# Schaltzeichen.net
KiCad netlist of a schematic drawn in EAGLE
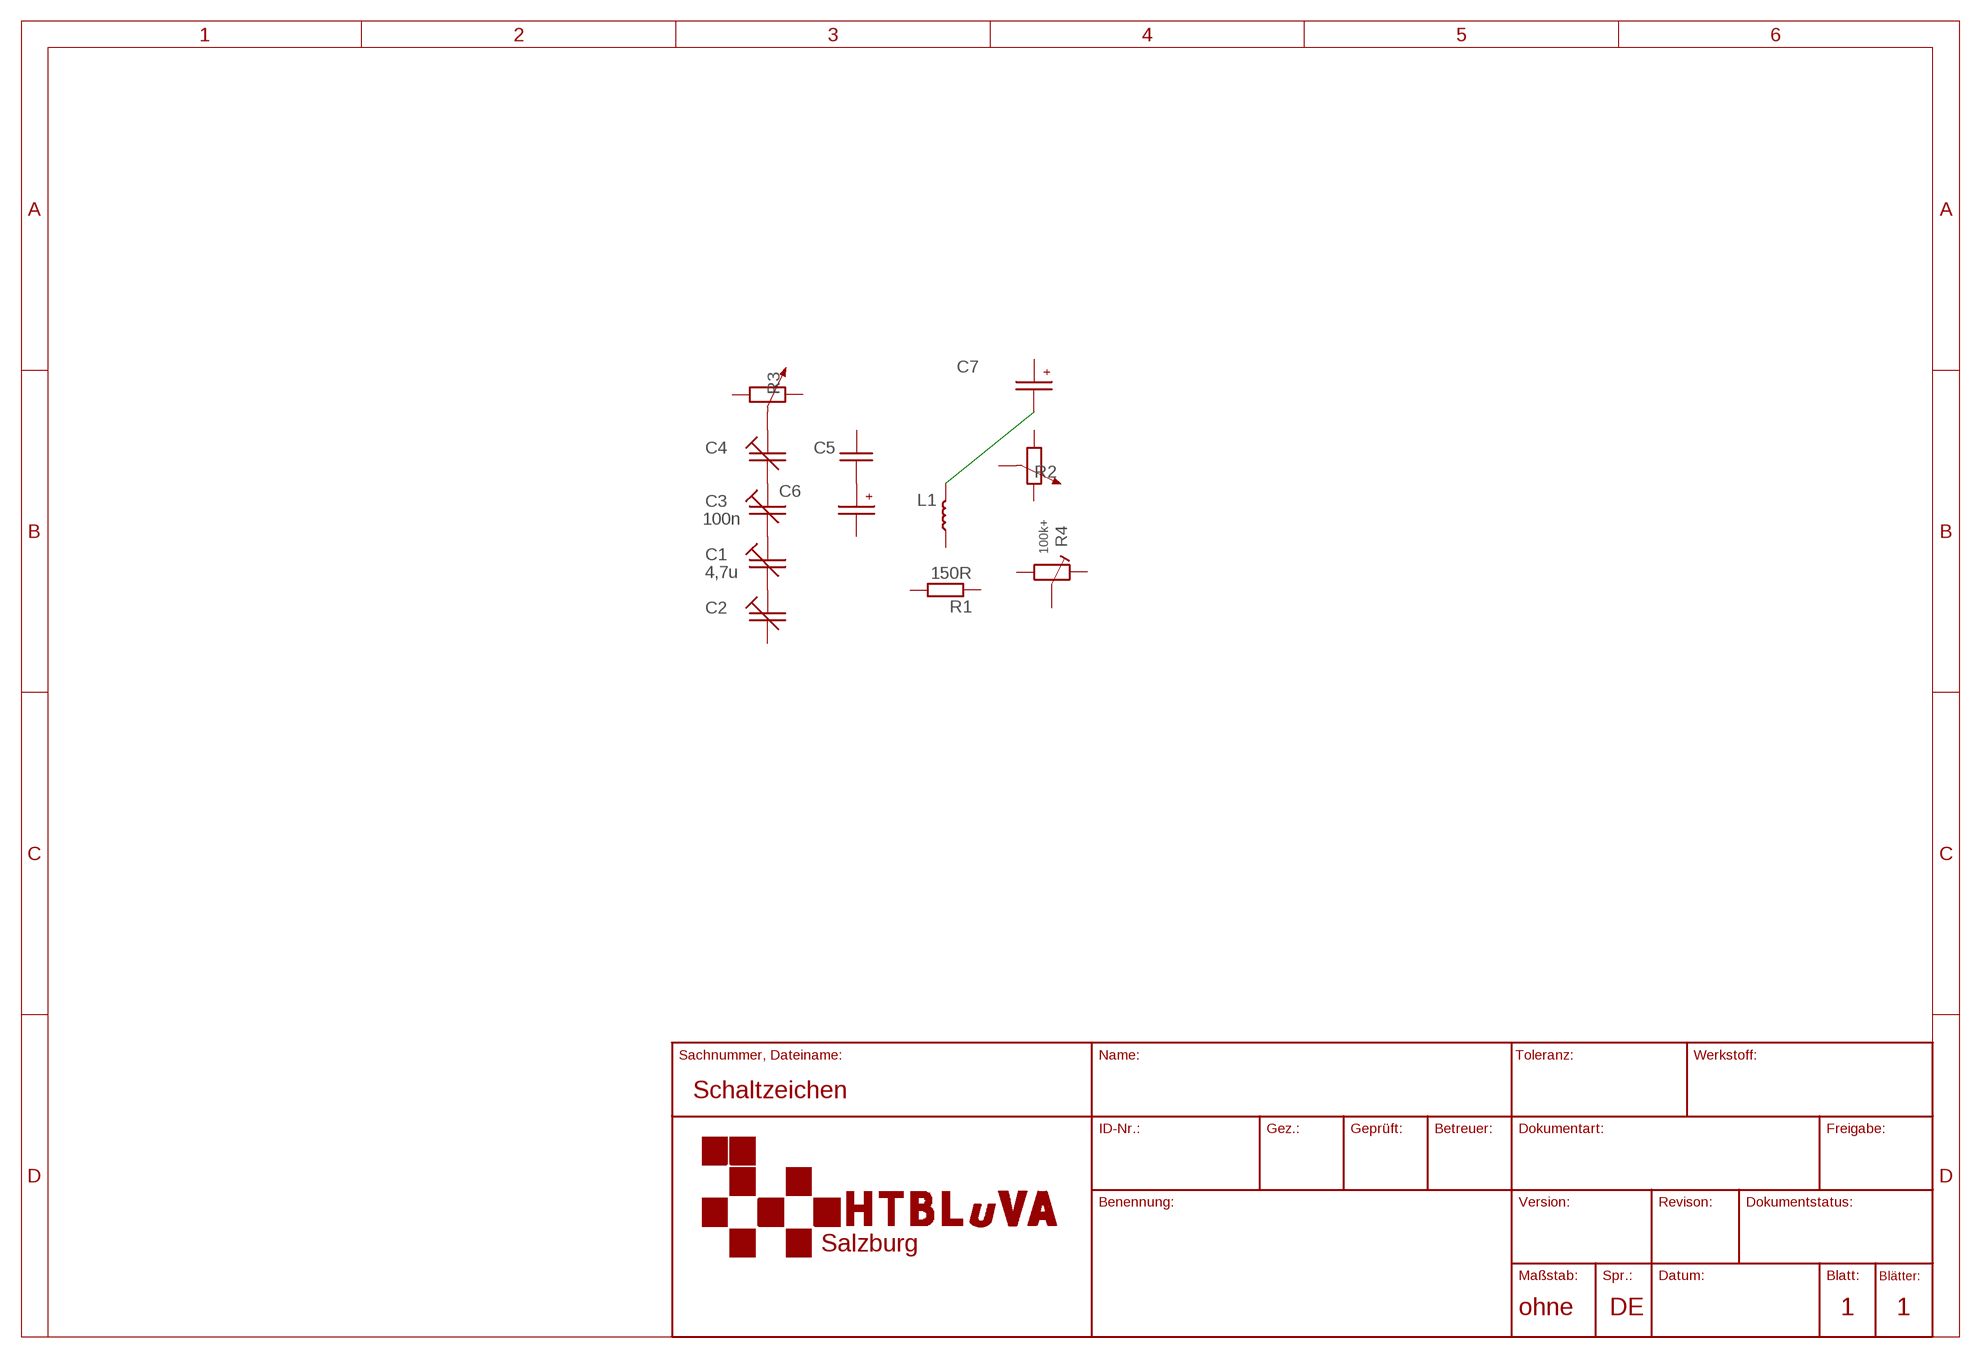
[diagram p0: schematic, sheet 1]

(export (version "E")
  (design (tool "Eeschema 10.0.6"))
  (components
    (comp (ref "C1")
      (value "4,7u")
      (footprint "eagle-import:CTRIM808-BC7.5")
      (libsource (lib "eagle-import") (part "C-TRIM-V_808-7.5"))
    )
    (comp (ref "C2")
      (value "C-TRIM-V_808-7.5")
      (footprint "eagle-import:CTRIM808-BC7.5")
      (libsource (lib "eagle-import") (part "C-TRIM-V_808-7.5"))
    )
    (comp (ref "C3")
      (value "100n")
      (footprint "eagle-import:CTRIM808-BC7.5")
      (libsource (lib "eagle-import") (part "C-TRIM-V_808-7.5"))
    )
    (comp (ref "C4")
      (value "C-TRIM-V_808-7.5")
      (footprint "eagle-import:CTRIM808-BC7.5")
      (libsource (lib "eagle-import") (part "C-TRIM-V_808-7.5"))
    )
    (comp (ref "C5")
      (value "C-V_025_050-045X075")
      (footprint "eagle-import:C025_050-045X075")
      (libsource (lib "eagle-import") (part "C-V_025_050-045X075"))
    )
    (comp (ref "C6")
      (value "CPOL-V_153CLV-0405")
      (footprint "eagle-import:153CLV-0405")
      (libsource (lib "eagle-import") (part "CPOL-V_153CLV-0405"))
    )
    (comp (ref "C7")
      (value "CPOL-V_153CLV-0405")
      (footprint "eagle-import:153CLV-0405")
      (libsource (lib "eagle-import") (part "CPOL-V_153CLV-0405"))
    )
    (comp (ref "L1")
      (value "L-V_L2012C")
      (footprint "eagle-import:L2012C")
      (libsource (lib "eagle-import") (part "L-V_L2012C"))
    )
    (comp (ref "R1")
      (value "150R")
      (footprint "eagle-import:P0613V")
      (libsource (lib "eagle-import") (part "R-H_0613/5V"))
    )
    (comp (ref "R2")
      (value "R-POT_V_PT-10")
      (footprint "eagle-import:PT-10")
      (libsource (lib "eagle-import") (part "R-POT_V_PT-10"))
    )
    (comp (ref "R3")
      (value "R-POT_V_PT-10")
      (footprint "eagle-import:PT-10")
      (libsource (lib "eagle-import") (part "R-POT_V_PT-10"))
    )
    (comp (ref "R4")
      (value "100k+")
      (footprint "eagle-import:RTRIM3296P")
      (libsource (lib "eagle-import") (part "R-TRIMM_V_3296P"))
    )
  )
  (nets
    (net (code "1") (name "Net-(C1-A)") (class "Default")
      (node (ref "C1") (pin "2") (pinfunction "A_2") (pintype "passive"))
      (node (ref "C2") (pin "1") (pinfunction "E_1") (pintype "passive"))
    )
    (net (code "2") (name "Net-(C1-E)") (class "Default")
      (node (ref "C1") (pin "1") (pinfunction "E_1") (pintype "passive"))
      (node (ref "C3") (pin "2") (pinfunction "A_2") (pintype "passive"))
    )
    (net (code "3") (name "Net-(C3-E)") (class "Default")
      (node (ref "C3") (pin "1") (pinfunction "E_1") (pintype "passive"))
      (node (ref "C4") (pin "2") (pinfunction "A_2") (pintype "passive"))
    )
    (net (code "4") (name "Net-(C4-E)") (class "Default")
      (node (ref "C4") (pin "1") (pinfunction "E_1") (pintype "passive"))
      (node (ref "R3") (pin "3") (pinfunction "3_3") (pintype "passive"))
    )
    (net (code "5") (name "Net-(C5-Pad2)") (class "Default")
      (node (ref "C5") (pin "2") (pinfunction "2_2") (pintype "passive"))
      (node (ref "C6") (pin "+") (pinfunction "+_+") (pintype "passive"))
    )
    (net (code "6") (name "Net-(C7-Pad-)") (class "Default")
      (node (ref "C7") (pin "-") (pinfunction "-_-") (pintype "passive"))
      (node (ref "L1") (pin "1") (pinfunction "1_1") (pintype "passive"))
    )
    (net (code "7") (name "unconnected-(C2-A-Pad2)") (class "Default")
      (node (ref "C2") (pin "2") (pinfunction "A_2") (pintype "passive"))
    )
    (net (code "8") (name "unconnected-(C5-Pad1)") (class "Default")
      (node (ref "C5") (pin "1") (pinfunction "1_1") (pintype "passive"))
    )
    (net (code "9") (name "unconnected-(C6-Pad-)") (class "Default")
      (node (ref "C6") (pin "-") (pinfunction "-_-") (pintype "passive"))
    )
    (net (code "10") (name "unconnected-(C7-Pad+)") (class "Default")
      (node (ref "C7") (pin "+") (pinfunction "+_+") (pintype "passive"))
    )
    (net (code "11") (name "unconnected-(L1-Pad2)") (class "Default")
      (node (ref "L1") (pin "2") (pinfunction "2_2") (pintype "passive"))
    )
    (net (code "12") (name "unconnected-(R1-Pad1)") (class "Default")
      (node (ref "R1") (pin "1") (pinfunction "1_1") (pintype "passive"))
    )
    (net (code "13") (name "unconnected-(R1-Pad2)") (class "Default")
      (node (ref "R1") (pin "2") (pinfunction "2_2") (pintype "passive"))
    )
    (net (code "14") (name "unconnected-(R2-Pad1)") (class "Default")
      (node (ref "R2") (pin "1") (pinfunction "1_1") (pintype "passive"))
    )
    (net (code "15") (name "unconnected-(R2-Pad2)") (class "Default")
      (node (ref "R2") (pin "2") (pinfunction "2_2") (pintype "passive"))
    )
    (net (code "16") (name "unconnected-(R2-Pad3)") (class "Default")
      (node (ref "R2") (pin "3") (pinfunction "3_3") (pintype "passive"))
    )
    (net (code "17") (name "unconnected-(R3-Pad1)") (class "Default")
      (node (ref "R3") (pin "1") (pinfunction "1_1") (pintype "passive"))
    )
    (net (code "18") (name "unconnected-(R3-Pad2)") (class "Default")
      (node (ref "R3") (pin "2") (pinfunction "2_2") (pintype "passive"))
    )
    (net (code "19") (name "unconnected-(R4-A-Pad1)") (class "Default")
      (node (ref "R4") (pin "1") (pinfunction "A_1") (pintype "passive"))
    )
    (net (code "20") (name "unconnected-(R4-E-Pad3)") (class "Default")
      (node (ref "R4") (pin "3") (pinfunction "E_3") (pintype "passive"))
    )
    (net (code "21") (name "unconnected-(R4-S-Pad2)") (class "Default")
      (node (ref "R4") (pin "2") (pinfunction "S_2") (pintype "passive"))
    )
  )
)
